# JackPots.net
KiCad netlist of a schematic drawn in EAGLE
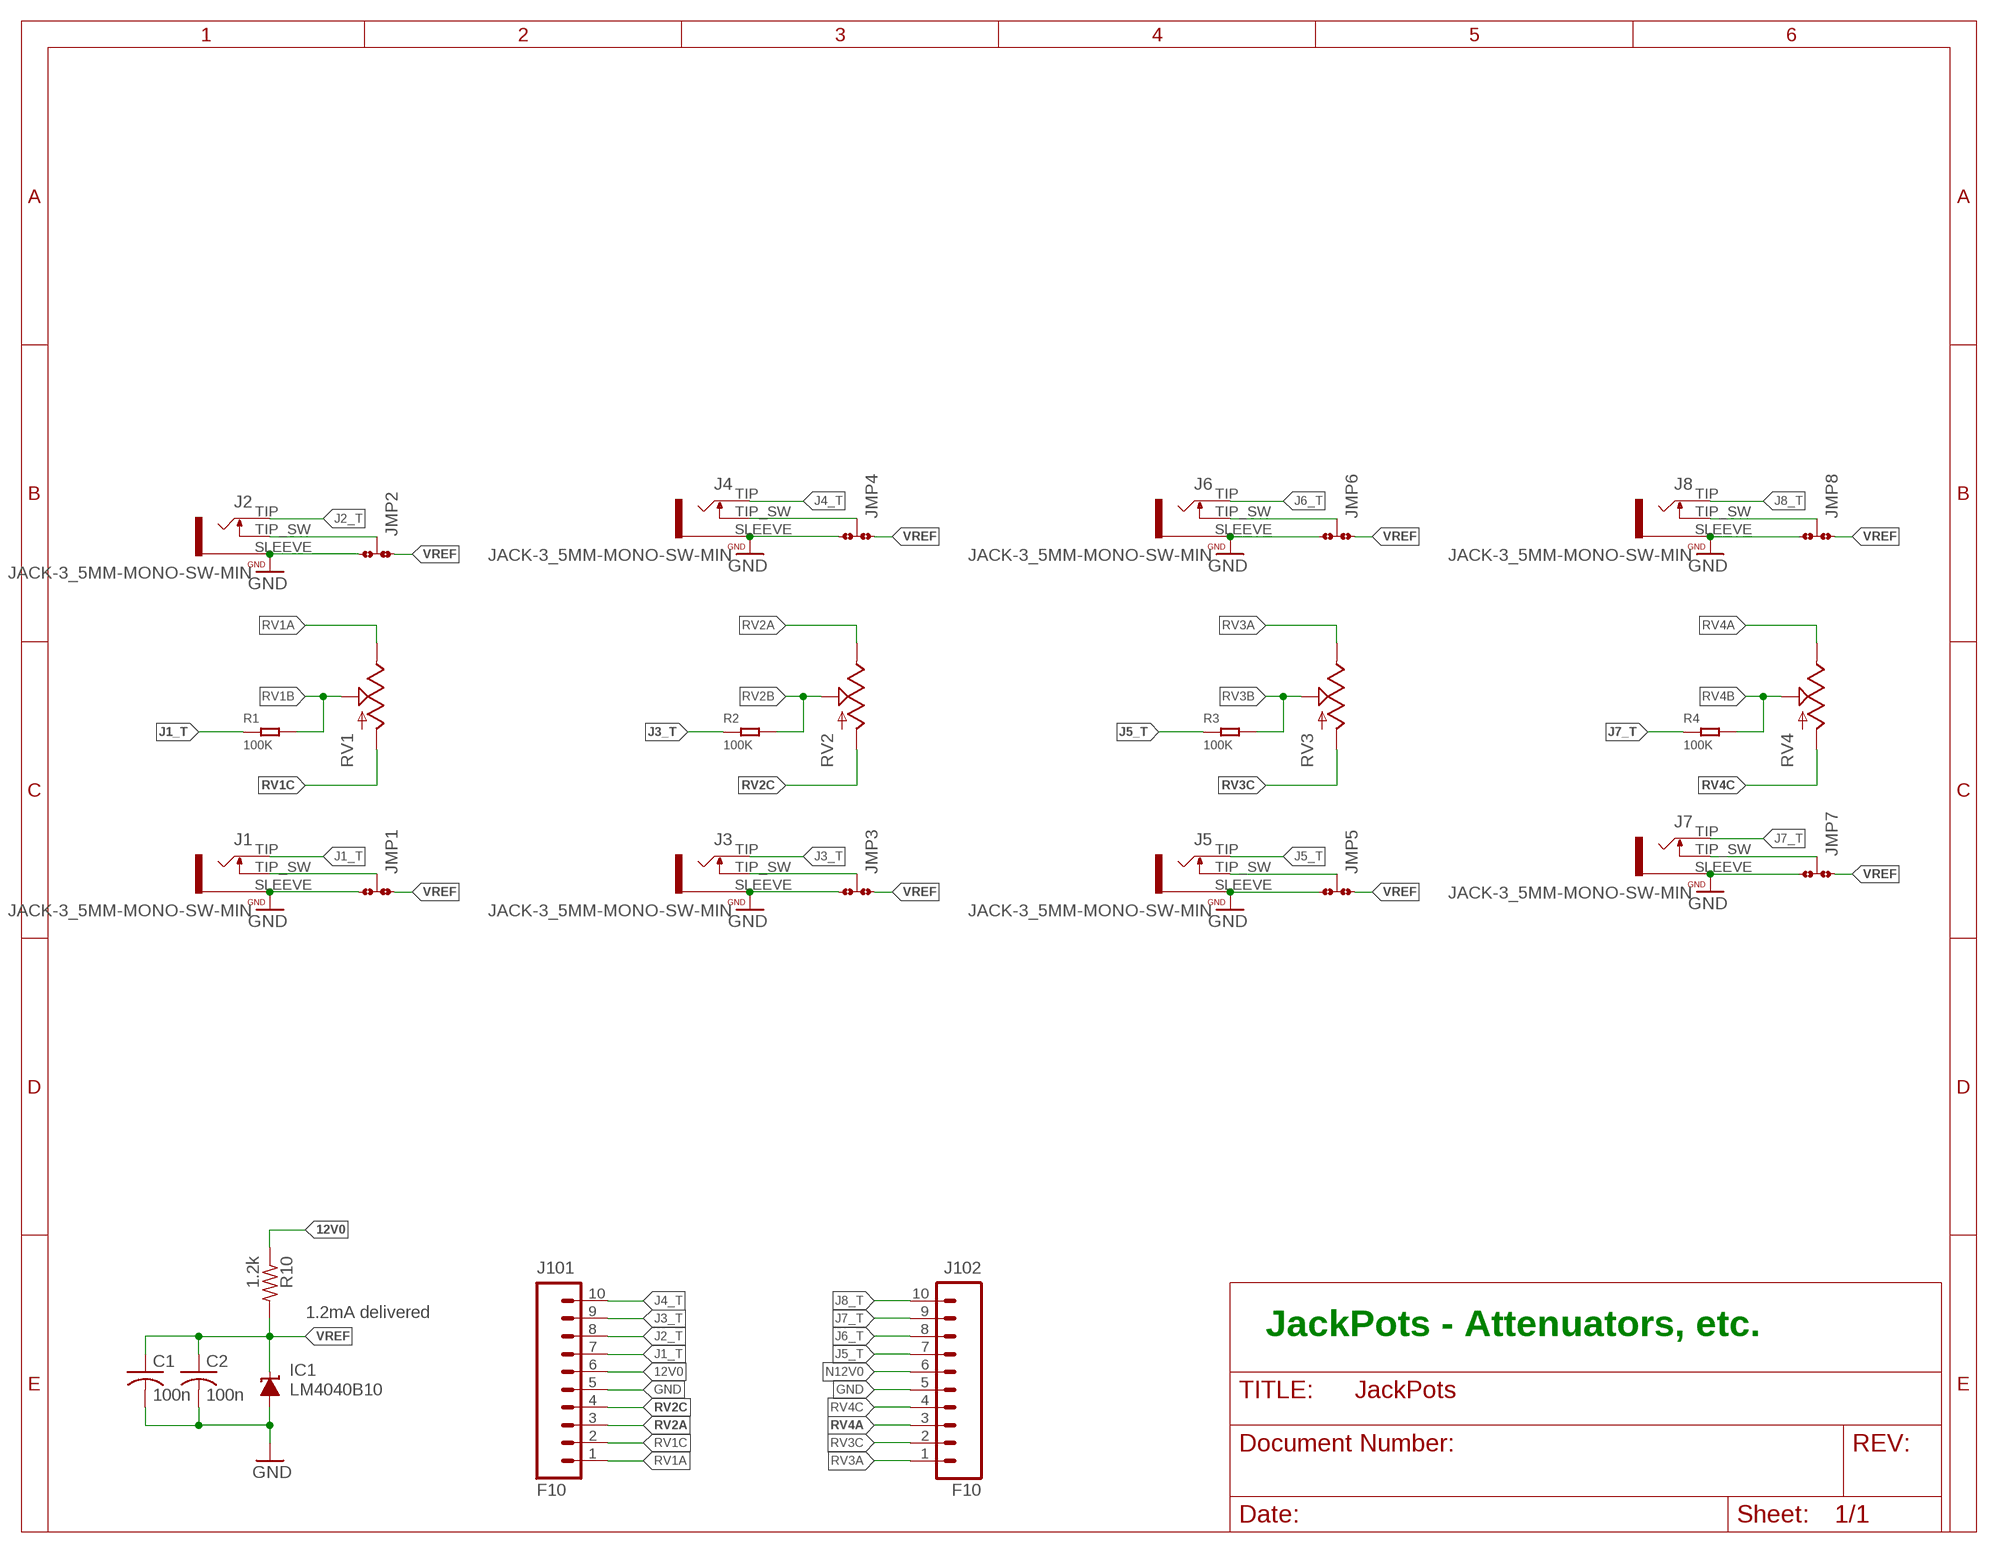
[diagram p0: schematic, sheet 1]

(export (version "E")
  (design (tool "Eeschema 10.0.6"))
  (components
    (comp (ref "C1")
      (value "100n")
      (footprint "eagle-import:C0603")
      (libsource (lib "eagle-import") (part "C-USC0603"))
    )
    (comp (ref "C2")
      (value "100n")
      (footprint "eagle-import:C0603")
      (libsource (lib "eagle-import") (part "C-USC0603"))
    )
    (comp (ref "IC1")
      (value "LM4040B10")
      (footprint "eagle-import:DBZ_R-PDSO-G3")
      (libsource (lib "eagle-import") (part "LM4041DBZB12"))
    )
    (comp (ref "J1")
      (value "JACK-3_5MM-MONO-SW-MIN")
      (footprint "eagle-import:WQP_PJ301M-MIN")
      (libsource (lib "eagle-import") (part "JACK-3_5MM-MONO-SW-MIN"))
    )
    (comp (ref "J2")
      (value "JACK-3_5MM-MONO-SW-MIN")
      (footprint "eagle-import:WQP_PJ301M-MIN")
      (libsource (lib "eagle-import") (part "JACK-3_5MM-MONO-SW-MIN"))
    )
    (comp (ref "J3")
      (value "JACK-3_5MM-MONO-SW-MIN")
      (footprint "eagle-import:WQP_PJ301M-MIN")
      (libsource (lib "eagle-import") (part "JACK-3_5MM-MONO-SW-MIN"))
    )
    (comp (ref "J4")
      (value "JACK-3_5MM-MONO-SW-MIN")
      (footprint "eagle-import:WQP_PJ301M-MIN")
      (libsource (lib "eagle-import") (part "JACK-3_5MM-MONO-SW-MIN"))
    )
    (comp (ref "J5")
      (value "JACK-3_5MM-MONO-SW-MIN")
      (footprint "eagle-import:WQP_PJ301M-MIN")
      (libsource (lib "eagle-import") (part "JACK-3_5MM-MONO-SW-MIN"))
    )
    (comp (ref "J6")
      (value "JACK-3_5MM-MONO-SW-MIN")
      (footprint "eagle-import:WQP_PJ301M-MIN")
      (libsource (lib "eagle-import") (part "JACK-3_5MM-MONO-SW-MIN"))
    )
    (comp (ref "J7")
      (value "JACK-3_5MM-MONO-SW-MIN")
      (footprint "eagle-import:WQP_PJ301M-MIN")
      (libsource (lib "eagle-import") (part "JACK-3_5MM-MONO-SW-MIN"))
    )
    (comp (ref "J8")
      (value "JACK-3_5MM-MONO-SW-MIN")
      (footprint "eagle-import:WQP_PJ301M-MIN")
      (libsource (lib "eagle-import") (part "JACK-3_5MM-MONO-SW-MIN"))
    )
    (comp (ref "J101")
      (value "F10")
      (footprint "eagle-import:1X10_OCTO")
      (libsource (lib "eagle-import") (part "M10SILK_FEMALE_PTH"))
    )
    (comp (ref "J102")
      (value "F10")
      (footprint "eagle-import:1X10_OCTO")
      (libsource (lib "eagle-import") (part "M10SILK_FEMALE_PTH"))
    )
    (comp (ref "JMP1")
      (value "JMP-3-NO-0603")
      (footprint "eagle-import:JMP-3-NO-0603")
      (libsource (lib "eagle-import") (part "JMP-3-NO-0603"))
    )
    (comp (ref "JMP2")
      (value "JMP-3-NO-0603")
      (footprint "eagle-import:JMP-3-NO-0603")
      (libsource (lib "eagle-import") (part "JMP-3-NO-0603"))
    )
    (comp (ref "JMP3")
      (value "JMP-3-NO-0603")
      (footprint "eagle-import:JMP-3-NO-0603")
      (libsource (lib "eagle-import") (part "JMP-3-NO-0603"))
    )
    (comp (ref "JMP4")
      (value "JMP-3-NO-0603")
      (footprint "eagle-import:JMP-3-NO-0603")
      (libsource (lib "eagle-import") (part "JMP-3-NO-0603"))
    )
    (comp (ref "JMP5")
      (value "JMP-3-NO-0603")
      (footprint "eagle-import:JMP-3-NO-0603")
      (libsource (lib "eagle-import") (part "JMP-3-NO-0603"))
    )
    (comp (ref "JMP6")
      (value "JMP-3-NO-0603")
      (footprint "eagle-import:JMP-3-NO-0603")
      (libsource (lib "eagle-import") (part "JMP-3-NO-0603"))
    )
    (comp (ref "JMP7")
      (value "JMP-3-NO-0603")
      (footprint "eagle-import:JMP-3-NO-0603")
      (libsource (lib "eagle-import") (part "JMP-3-NO-0603"))
    )
    (comp (ref "JMP8")
      (value "JMP-3-NO-0603")
      (footprint "eagle-import:JMP-3-NO-0603")
      (libsource (lib "eagle-import") (part "JMP-3-NO-0603"))
    )
    (comp (ref "R1")
      (value "100K")
      (footprint "eagle-import:R0603")
      (fields (field (name "MPN") "RC0603FR-07100KL"))
      (libsource (lib "eagle-import") (part "SMD-RES-100K-1%-1/10W(0603)"))
    )
    (comp (ref "R2")
      (value "100K")
      (footprint "eagle-import:R0603")
      (fields (field (name "MPN") "RC0603FR-07100KL"))
      (libsource (lib "eagle-import") (part "SMD-RES-100K-1%-1/10W(0603)"))
    )
    (comp (ref "R3")
      (value "100K")
      (footprint "eagle-import:R0603")
      (fields (field (name "MPN") "RC0603FR-07100KL"))
      (libsource (lib "eagle-import") (part "SMD-RES-100K-1%-1/10W(0603)"))
    )
    (comp (ref "R4")
      (value "100K")
      (footprint "eagle-import:R0603")
      (fields (field (name "MPN") "RC0603FR-07100KL"))
      (libsource (lib "eagle-import") (part "SMD-RES-100K-1%-1/10W(0603)"))
    )
    (comp (ref "R10")
      (value "1.2k")
      (footprint "eagle-import:R0603")
      (libsource (lib "eagle-import") (part "R-US_R0603"))
    )
    (comp (ref "RV1")
      (value "POT")
      (footprint "eagle-import:ALPS_POT")
      (libsource (lib "eagle-import") (part "POT"))
    )
    (comp (ref "RV2")
      (value "POT")
      (footprint "eagle-import:ALPS_POT")
      (libsource (lib "eagle-import") (part "POT"))
    )
    (comp (ref "RV3")
      (value "POT")
      (footprint "eagle-import:ALPS_POT")
      (libsource (lib "eagle-import") (part "POT"))
    )
    (comp (ref "RV4")
      (value "POT")
      (footprint "eagle-import:ALPS_POT")
      (libsource (lib "eagle-import") (part "POT"))
    )
  )
  (nets
    (net (code "1") (name "12V0") (class "Default")
      (node (ref "J101") (pin "6") (pinfunction "6_6") (pintype "passive"))
      (node (ref "R10") (pin "1") (pinfunction "1_1") (pintype "passive"))
    )
    (net (code "2") (name "GND") (class "Default")
      (node (ref "C1") (pin "2") (pinfunction "2_2") (pintype "passive"))
      (node (ref "C2") (pin "2") (pinfunction "2_2") (pintype "passive"))
      (node (ref "IC1") (pin "2") (pinfunction "A_2") (pintype "passive"))
      (node (ref "J1") (pin "SLEEVE") (pinfunction "SLEEVE_SLEEVE") (pintype "passive"))
      (node (ref "J101") (pin "5") (pinfunction "5_5") (pintype "passive"))
      (node (ref "J102") (pin "5") (pinfunction "5_5") (pintype "passive"))
      (node (ref "J2") (pin "SLEEVE") (pinfunction "SLEEVE_SLEEVE") (pintype "passive"))
      (node (ref "J3") (pin "SLEEVE") (pinfunction "SLEEVE_SLEEVE") (pintype "passive"))
      (node (ref "J4") (pin "SLEEVE") (pinfunction "SLEEVE_SLEEVE") (pintype "passive"))
      (node (ref "J5") (pin "SLEEVE") (pinfunction "SLEEVE_SLEEVE") (pintype "passive"))
      (node (ref "J6") (pin "SLEEVE") (pinfunction "SLEEVE_SLEEVE") (pintype "passive"))
      (node (ref "J7") (pin "SLEEVE") (pinfunction "SLEEVE_SLEEVE") (pintype "passive"))
      (node (ref "J8") (pin "SLEEVE") (pinfunction "SLEEVE_SLEEVE") (pintype "passive"))
      (node (ref "JMP1") (pin "3") (pinfunction "3_3") (pintype "passive"))
      (node (ref "JMP2") (pin "3") (pinfunction "3_3") (pintype "passive"))
      (node (ref "JMP3") (pin "3") (pinfunction "3_3") (pintype "passive"))
      (node (ref "JMP4") (pin "3") (pinfunction "3_3") (pintype "passive"))
      (node (ref "JMP5") (pin "3") (pinfunction "3_3") (pintype "passive"))
      (node (ref "JMP6") (pin "3") (pinfunction "3_3") (pintype "passive"))
      (node (ref "JMP7") (pin "3") (pinfunction "3_3") (pintype "passive"))
      (node (ref "JMP8") (pin "3") (pinfunction "3_3") (pintype "passive"))
    )
    (net (code "3") (name "J1_T") (class "Default")
      (node (ref "J1") (pin "TIP") (pinfunction "TIP_TIP") (pintype "passive"))
      (node (ref "J101") (pin "7") (pinfunction "7_7") (pintype "passive"))
      (node (ref "R1") (pin "1") (pinfunction "1_1") (pintype "passive"))
    )
    (net (code "4") (name "J2_T") (class "Default")
      (node (ref "J101") (pin "8") (pinfunction "8_8") (pintype "passive"))
      (node (ref "J2") (pin "TIP") (pinfunction "TIP_TIP") (pintype "passive"))
    )
    (net (code "5") (name "J3_T") (class "Default")
      (node (ref "J101") (pin "9") (pinfunction "9_9") (pintype "passive"))
      (node (ref "J3") (pin "TIP") (pinfunction "TIP_TIP") (pintype "passive"))
      (node (ref "R2") (pin "1") (pinfunction "1_1") (pintype "passive"))
    )
    (net (code "6") (name "J4_T") (class "Default")
      (node (ref "J101") (pin "10") (pinfunction "10_10") (pintype "passive"))
      (node (ref "J4") (pin "TIP") (pinfunction "TIP_TIP") (pintype "passive"))
    )
    (net (code "7") (name "J5_T") (class "Default")
      (node (ref "J102") (pin "7") (pinfunction "7_7") (pintype "passive"))
      (node (ref "J5") (pin "TIP") (pinfunction "TIP_TIP") (pintype "passive"))
      (node (ref "R3") (pin "1") (pinfunction "1_1") (pintype "passive"))
    )
    (net (code "8") (name "J6_T") (class "Default")
      (node (ref "J102") (pin "8") (pinfunction "8_8") (pintype "passive"))
      (node (ref "J6") (pin "TIP") (pinfunction "TIP_TIP") (pintype "passive"))
    )
    (net (code "9") (name "J7_T") (class "Default")
      (node (ref "J102") (pin "9") (pinfunction "9_9") (pintype "passive"))
      (node (ref "J7") (pin "TIP") (pinfunction "TIP_TIP") (pintype "passive"))
      (node (ref "R4") (pin "1") (pinfunction "1_1") (pintype "passive"))
    )
    (net (code "10") (name "J8_T") (class "Default")
      (node (ref "J102") (pin "10") (pinfunction "10_10") (pintype "passive"))
      (node (ref "J8") (pin "TIP") (pinfunction "TIP_TIP") (pintype "passive"))
    )
    (net (code "11") (name "N12V0") (class "Default")
      (node (ref "J102") (pin "6") (pinfunction "6_6") (pintype "passive"))
    )
    (net (code "12") (name "Net-(J1-PadTIP_SW)") (class "Default")
      (node (ref "J1") (pin "TIP_SW") (pinfunction "TIP_SW_TIP_SW") (pintype "passive"))
      (node (ref "JMP1") (pin "2") (pinfunction "2_2") (pintype "passive"))
    )
    (net (code "13") (name "Net-(J2-PadTIP_SW)") (class "Default")
      (node (ref "J2") (pin "TIP_SW") (pinfunction "TIP_SW_TIP_SW") (pintype "passive"))
      (node (ref "JMP2") (pin "2") (pinfunction "2_2") (pintype "passive"))
    )
    (net (code "14") (name "Net-(J3-PadTIP_SW)") (class "Default")
      (node (ref "J3") (pin "TIP_SW") (pinfunction "TIP_SW_TIP_SW") (pintype "passive"))
      (node (ref "JMP3") (pin "2") (pinfunction "2_2") (pintype "passive"))
    )
    (net (code "15") (name "Net-(J4-PadTIP_SW)") (class "Default")
      (node (ref "J4") (pin "TIP_SW") (pinfunction "TIP_SW_TIP_SW") (pintype "passive"))
      (node (ref "JMP4") (pin "2") (pinfunction "2_2") (pintype "passive"))
    )
    (net (code "16") (name "Net-(J5-PadTIP_SW)") (class "Default")
      (node (ref "J5") (pin "TIP_SW") (pinfunction "TIP_SW_TIP_SW") (pintype "passive"))
      (node (ref "JMP5") (pin "2") (pinfunction "2_2") (pintype "passive"))
    )
    (net (code "17") (name "Net-(J6-PadTIP_SW)") (class "Default")
      (node (ref "J6") (pin "TIP_SW") (pinfunction "TIP_SW_TIP_SW") (pintype "passive"))
      (node (ref "JMP6") (pin "2") (pinfunction "2_2") (pintype "passive"))
    )
    (net (code "18") (name "Net-(J7-PadTIP_SW)") (class "Default")
      (node (ref "J7") (pin "TIP_SW") (pinfunction "TIP_SW_TIP_SW") (pintype "passive"))
      (node (ref "JMP7") (pin "2") (pinfunction "2_2") (pintype "passive"))
    )
    (net (code "19") (name "Net-(J8-PadTIP_SW)") (class "Default")
      (node (ref "J8") (pin "TIP_SW") (pinfunction "TIP_SW_TIP_SW") (pintype "passive"))
      (node (ref "JMP8") (pin "2") (pinfunction "2_2") (pintype "passive"))
    )
    (net (code "20") (name "RV1A") (class "Default")
      (node (ref "J101") (pin "1") (pinfunction "1_1") (pintype "passive"))
      (node (ref "RV1") (pin "P$1") (pinfunction "3_P$1") (pintype "passive"))
    )
    (net (code "21") (name "RV1B") (class "Default")
      (node (ref "R1") (pin "2") (pinfunction "2_2") (pintype "passive"))
      (node (ref "RV1") (pin "P$2") (pinfunction "2_P$2") (pintype "passive"))
    )
    (net (code "22") (name "RV1C") (class "Default")
      (node (ref "J101") (pin "2") (pinfunction "2_2") (pintype "passive"))
      (node (ref "RV1") (pin "P$3") (pinfunction "1_P$3") (pintype "passive"))
    )
    (net (code "23") (name "RV2A") (class "Default")
      (node (ref "J101") (pin "3") (pinfunction "3_3") (pintype "passive"))
      (node (ref "RV2") (pin "P$1") (pinfunction "3_P$1") (pintype "passive"))
    )
    (net (code "24") (name "RV2B") (class "Default")
      (node (ref "R2") (pin "2") (pinfunction "2_2") (pintype "passive"))
      (node (ref "RV2") (pin "P$2") (pinfunction "2_P$2") (pintype "passive"))
    )
    (net (code "25") (name "RV2C") (class "Default")
      (node (ref "J101") (pin "4") (pinfunction "4_4") (pintype "passive"))
      (node (ref "RV2") (pin "P$3") (pinfunction "1_P$3") (pintype "passive"))
    )
    (net (code "26") (name "RV3A") (class "Default")
      (node (ref "J102") (pin "1") (pinfunction "1_1") (pintype "passive"))
      (node (ref "RV3") (pin "P$1") (pinfunction "3_P$1") (pintype "passive"))
    )
    (net (code "27") (name "RV3B") (class "Default")
      (node (ref "R3") (pin "2") (pinfunction "2_2") (pintype "passive"))
      (node (ref "RV3") (pin "P$2") (pinfunction "2_P$2") (pintype "passive"))
    )
    (net (code "28") (name "RV3C") (class "Default")
      (node (ref "J102") (pin "2") (pinfunction "2_2") (pintype "passive"))
      (node (ref "RV3") (pin "P$3") (pinfunction "1_P$3") (pintype "passive"))
    )
    (net (code "29") (name "RV4A") (class "Default")
      (node (ref "J102") (pin "3") (pinfunction "3_3") (pintype "passive"))
      (node (ref "RV4") (pin "P$1") (pinfunction "3_P$1") (pintype "passive"))
    )
    (net (code "30") (name "RV4B") (class "Default")
      (node (ref "R4") (pin "2") (pinfunction "2_2") (pintype "passive"))
      (node (ref "RV4") (pin "P$2") (pinfunction "2_P$2") (pintype "passive"))
    )
    (net (code "31") (name "RV4C") (class "Default")
      (node (ref "J102") (pin "4") (pinfunction "4_4") (pintype "passive"))
      (node (ref "RV4") (pin "P$3") (pinfunction "1_P$3") (pintype "passive"))
    )
    (net (code "32") (name "VREF") (class "Default")
      (node (ref "C1") (pin "1") (pinfunction "1_1") (pintype "passive"))
      (node (ref "C2") (pin "1") (pinfunction "1_1") (pintype "passive"))
      (node (ref "IC1") (pin "1") (pinfunction "C_1") (pintype "passive"))
      (node (ref "JMP1") (pin "1") (pinfunction "1_1") (pintype "passive"))
      (node (ref "JMP2") (pin "1") (pinfunction "1_1") (pintype "passive"))
      (node (ref "JMP3") (pin "1") (pinfunction "1_1") (pintype "passive"))
      (node (ref "JMP4") (pin "1") (pinfunction "1_1") (pintype "passive"))
      (node (ref "JMP5") (pin "1") (pinfunction "1_1") (pintype "passive"))
      (node (ref "JMP6") (pin "1") (pinfunction "1_1") (pintype "passive"))
      (node (ref "JMP7") (pin "1") (pinfunction "1_1") (pintype "passive"))
      (node (ref "JMP8") (pin "1") (pinfunction "1_1") (pintype "passive"))
      (node (ref "R10") (pin "2") (pinfunction "2_2") (pintype "passive"))
    )
  )
)
